# Qwiic_BME688.net
KiCad netlist of a schematic drawn in EAGLE
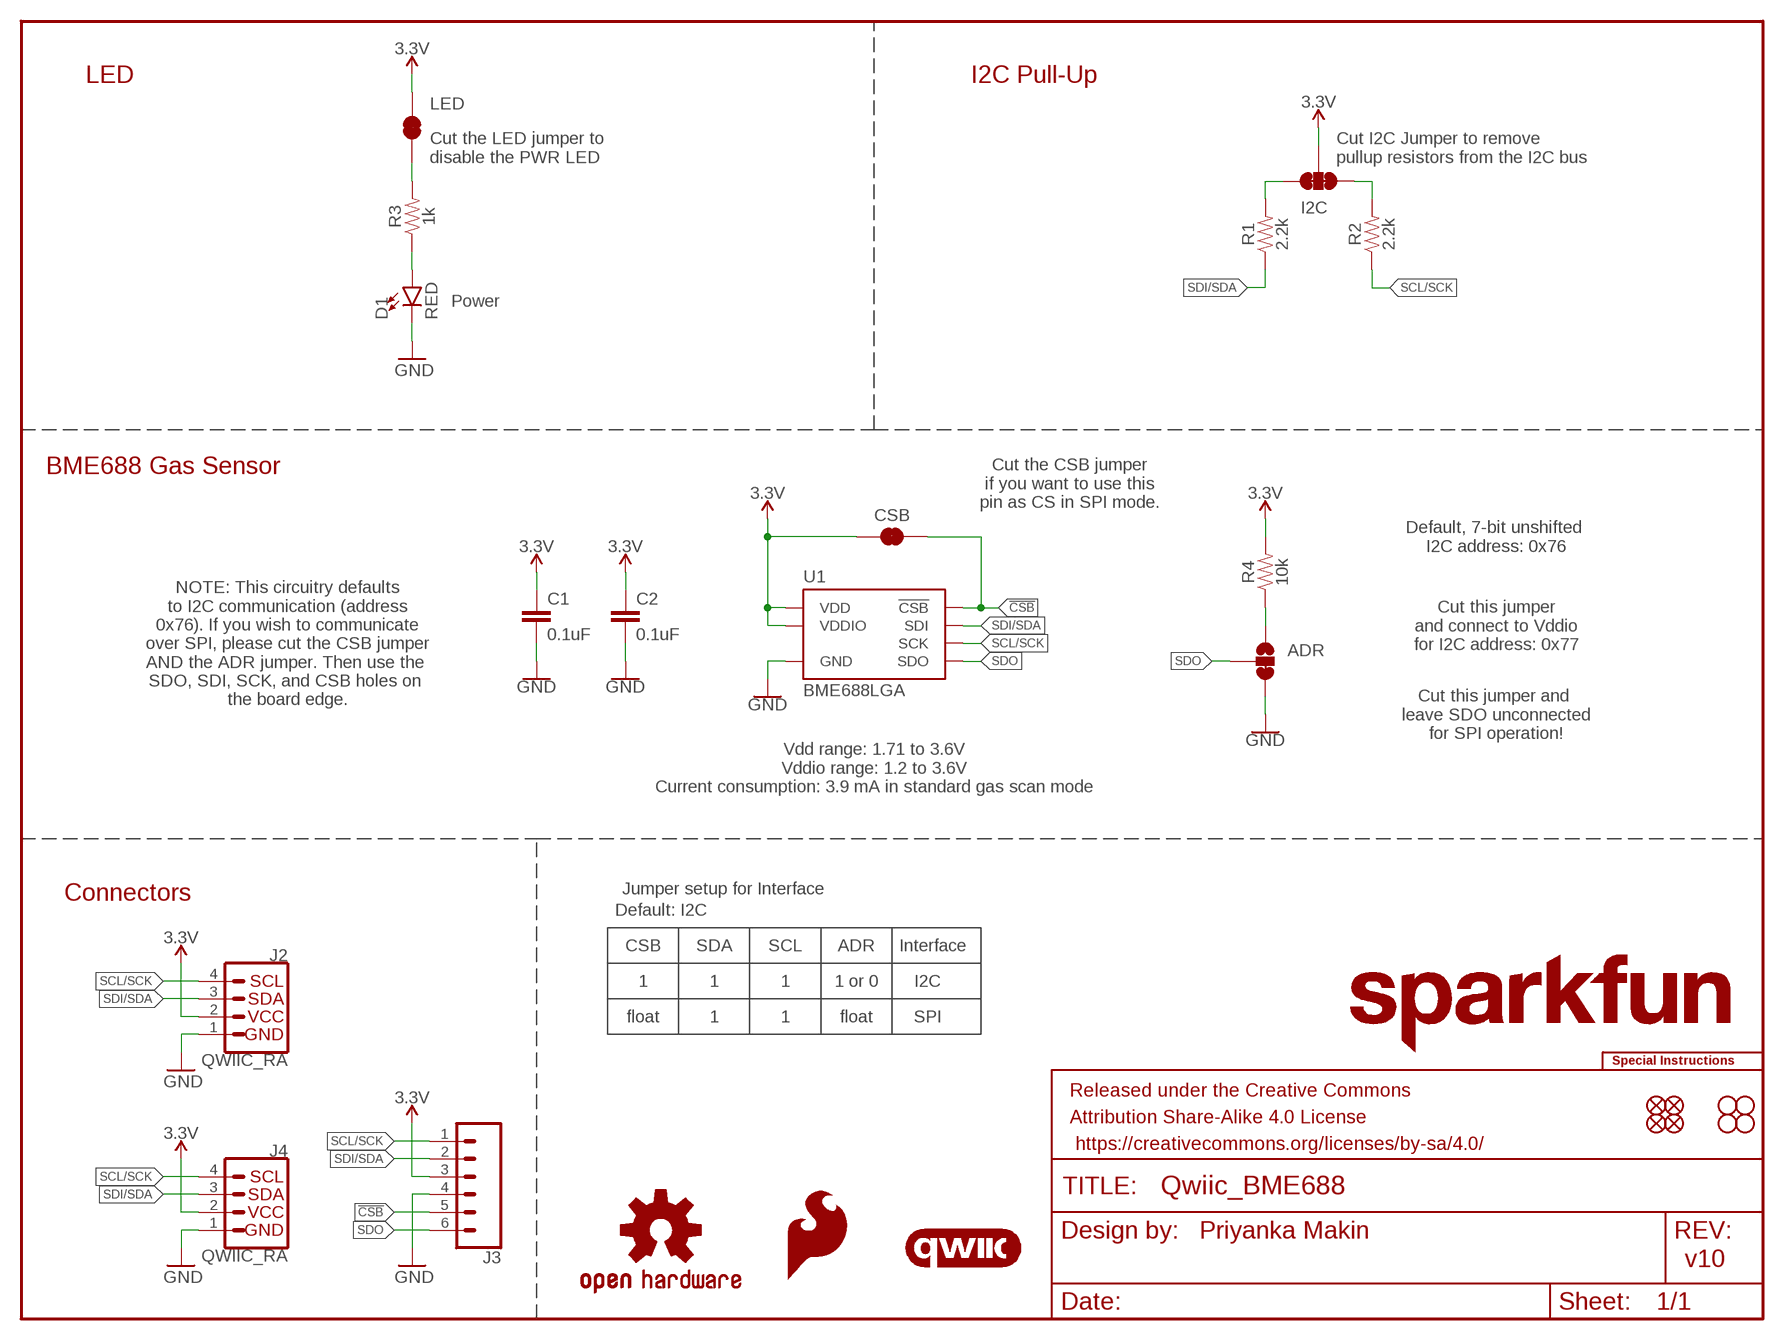
[diagram p0: schematic, sheet 1]

(export (version "E")
  (design (tool "Eeschema 10.0.6"))
  (components
    (comp (ref "ADR")
      (value "JUMPER-SMT_3_1-NC_TRACE_SILK")
      (footprint "eagle-import:SMT-JUMPER_3_1-NC_TRACE_SILK")
      (libsource (lib "eagle-import") (part "JUMPER-SMT_3_1-NC_TRACE_SILK"))
    )
    (comp (ref "C1")
      (value "0.1uF")
      (footprint "eagle-import:0603")
      (libsource (lib "eagle-import") (part "0.1UF-0603-100V-10%"))
    )
    (comp (ref "C2")
      (value "0.1uF")
      (footprint "eagle-import:0603")
      (libsource (lib "eagle-import") (part "0.1UF-0603-100V-10%"))
    )
    (comp (ref "CSB")
      (value "JUMPER-SMT_2_NC_TRACE_SILK")
      (footprint "eagle-import:SMT-JUMPER_2_NC_TRACE_SILK")
      (libsource (lib "eagle-import") (part "JUMPER-SMT_2_NC_TRACE_SILK"))
    )
    (comp (ref "D1")
      (value "RED")
      (footprint "eagle-import:LED-0603")
      (libsource (lib "eagle-import") (part "LED-RED0603"))
    )
    (comp (ref "FRAME1")
      (value "FRAME-LETTER")
      (footprint "eagle-import:CREATIVE_COMMONS")
      (libsource (lib "eagle-import") (part "FRAME-LETTER"))
    )
    (comp (ref "I2C")
      (value "JUMPER-SMT_3_2-NC_TRACE_SILK")
      (footprint "eagle-import:SMT-JUMPER_3_2-NC_TRACE_SILK")
      (libsource (lib "eagle-import") (part "JUMPER-SMT_3_2-NC_TRACE_SILK"))
    )
    (comp (ref "J2")
      (value "QWIIC_RA")
      (footprint "eagle-import:JST04_1MM_RA")
      (libsource (lib "eagle-import") (part "QWIIC_CONNECTORJS-1MM"))
    )
    (comp (ref "J3")
      (value "CONN_06NO_SILK_NO_POP")
      (footprint "eagle-import:1X06_NO_SILK")
      (libsource (lib "eagle-import") (part "CONN_06NO_SILK_NO_POP"))
    )
    (comp (ref "J4")
      (value "QWIIC_RA")
      (footprint "eagle-import:JST04_1MM_RA")
      (libsource (lib "eagle-import") (part "QWIIC_CONNECTORJS-1MM"))
    )
    (comp (ref "JP1")
      (value "FIDUCIALUFIDUCIAL")
      (footprint "eagle-import:FIDUCIAL-MICRO")
      (libsource (lib "eagle-import") (part "FIDUCIALUFIDUCIAL"))
    )
    (comp (ref "JP2")
      (value "FIDUCIALUFIDUCIAL")
      (footprint "eagle-import:FIDUCIAL-MICRO")
      (libsource (lib "eagle-import") (part "FIDUCIALUFIDUCIAL"))
    )
    (comp (ref "JP3")
      (value "STAND-OFF")
      (footprint "eagle-import:STAND-OFF")
      (libsource (lib "eagle-import") (part "STAND-OFF"))
    )
    (comp (ref "JP4")
      (value "STAND-OFF")
      (footprint "eagle-import:STAND-OFF")
      (libsource (lib "eagle-import") (part "STAND-OFF"))
    )
    (comp (ref "JP5")
      (value "FIDUCIALUFIDUCIAL")
      (footprint "eagle-import:FIDUCIAL-MICRO")
      (libsource (lib "eagle-import") (part "FIDUCIALUFIDUCIAL"))
    )
    (comp (ref "JP6")
      (value "FIDUCIALUFIDUCIAL")
      (footprint "eagle-import:FIDUCIAL-MICRO")
      (libsource (lib "eagle-import") (part "FIDUCIALUFIDUCIAL"))
    )
    (comp (ref "JP7")
      (value "STAND-OFF")
      (footprint "eagle-import:STAND-OFF")
      (libsource (lib "eagle-import") (part "STAND-OFF"))
    )
    (comp (ref "JP8")
      (value "STAND-OFF")
      (footprint "eagle-import:STAND-OFF")
      (libsource (lib "eagle-import") (part "STAND-OFF"))
    )
    (comp (ref "LED")
      (value "JUMPER-SMT_2_NC_TRACE_SILK")
      (footprint "eagle-import:SMT-JUMPER_2_NC_TRACE_SILK")
      (libsource (lib "eagle-import") (part "JUMPER-SMT_2_NC_TRACE_SILK"))
    )
    (comp (ref "LOGO1")
      (value "SPECIAL_INSTRUCTIONS-ORDERING")
      (footprint "eagle-import:ORDERING_INSTRUCTIONS")
      (libsource (lib "eagle-import") (part "SPECIAL_INSTRUCTIONS-ORDERING"))
    )
    (comp (ref "LOGO2")
      (value "QWIIC_LOGO_5MM")
      (footprint "eagle-import:QWIIC_5MM")
      (libsource (lib "eagle-import") (part "QWIIC_LOGO_5MM"))
    )
    (comp (ref "LOGO3")
      (value "SFE_LOGO_NAME.1_INCH")
      (footprint "eagle-import:SFE_LOGO_NAME_.1")
      (libsource (lib "eagle-import") (part "SFE_LOGO_NAME.1_INCH"))
    )
    (comp (ref "LOGO4")
      (value "SFE_LOGO_FLAME.1_INCH")
      (footprint "eagle-import:SFE_LOGO_FLAME_.1")
      (libsource (lib "eagle-import") (part "SFE_LOGO_FLAME.1_INCH"))
    )
    (comp (ref "LOGO5")
      (value "OSHW-LOGOS")
      (footprint "eagle-import:OSHW-LOGO-S")
      (libsource (lib "eagle-import") (part "OSHW-LOGOS"))
    )
    (comp (ref "LOGO6")
      (value "SFE_LOGO_NAME.1_INCH")
      (footprint "eagle-import:SFE_LOGO_NAME_.1")
      (libsource (lib "eagle-import") (part "SFE_LOGO_NAME.1_INCH"))
    )
    (comp (ref "R1")
      (value "2.2k")
      (footprint "eagle-import:0603")
      (libsource (lib "eagle-import") (part "2.2KOHM-0603-1/10W-1%"))
    )
    (comp (ref "R2")
      (value "2.2k")
      (footprint "eagle-import:0603")
      (libsource (lib "eagle-import") (part "2.2KOHM-0603-1/10W-1%"))
    )
    (comp (ref "R3")
      (value "1k")
      (footprint "eagle-import:0603")
      (libsource (lib "eagle-import") (part "1KOHM-0603-1/10W-1%"))
    )
    (comp (ref "R4")
      (value "10k")
      (footprint "eagle-import:0603")
      (libsource (lib "eagle-import") (part "10KOHM-0603-1/10W-1%"))
    )
    (comp (ref "U1")
      (value "BME688LGA")
      (footprint "eagle-import:LGA_8PIN")
      (libsource (lib "eagle-import") (part "BME688LGA"))
    )
  )
  (nets
    (net (code "1") (name "/~{CSB}") (class "Default")
      (node (ref "CSB") (pin "2") (pinfunction "2_2") (pintype "passive"))
      (node (ref "J3") (pin "5") (pinfunction "5_5") (pintype "passive"))
      (node (ref "U1") (pin "2") (pinfunction "~{CSB}_2") (pintype "power_in"))
    )
    (net (code "2") (name "3.3V") (class "Default")
      (node (ref "C1") (pin "1") (pinfunction "1_1") (pintype "passive"))
      (node (ref "C2") (pin "1") (pinfunction "1_1") (pintype "passive"))
      (node (ref "CSB") (pin "1") (pinfunction "1_1") (pintype "passive"))
      (node (ref "I2C") (pin "2") (pinfunction "2_2") (pintype "passive"))
      (node (ref "J2") (pin "2") (pinfunction "2_2") (pintype "power_in"))
      (node (ref "J3") (pin "3") (pinfunction "3_3") (pintype "passive"))
      (node (ref "J4") (pin "2") (pinfunction "2_2") (pintype "power_in"))
      (node (ref "LED") (pin "2") (pinfunction "2_2") (pintype "passive"))
      (node (ref "R4") (pin "2") (pinfunction "2_2") (pintype "passive"))
      (node (ref "U1") (pin "6") (pinfunction "VDDIO_6") (pintype "power_in"))
      (node (ref "U1") (pin "8") (pinfunction "VDD_8") (pintype "power_in"))
    )
    (net (code "3") (name "GND") (class "Default")
      (node (ref "ADR") (pin "3") (pinfunction "3_3") (pintype "passive"))
      (node (ref "C1") (pin "2") (pinfunction "2_2") (pintype "passive"))
      (node (ref "C2") (pin "2") (pinfunction "2_2") (pintype "passive"))
      (node (ref "D1") (pin "C") (pinfunction "C_C") (pintype "passive"))
      (node (ref "J2") (pin "1") (pinfunction "1_1") (pintype "power_in"))
      (node (ref "J3") (pin "4") (pinfunction "4_4") (pintype "passive"))
      (node (ref "J4") (pin "1") (pinfunction "1_1") (pintype "power_in"))
      (node (ref "U1") (pin "1") (pinfunction "GND_1") (pintype "power_in"))
      (node (ref "U1") (pin "7") (pinfunction "GND_7") (pintype "power_in"))
    )
    (net (code "4") (name "Net-(ADR-Pad1)") (class "Default")
      (node (ref "ADR") (pin "1") (pinfunction "1_1") (pintype "passive"))
      (node (ref "R4") (pin "1") (pinfunction "1_1") (pintype "passive"))
    )
    (net (code "5") (name "Net-(D1-PadA)") (class "Default")
      (node (ref "D1") (pin "A") (pinfunction "A_A") (pintype "passive"))
      (node (ref "R3") (pin "1") (pinfunction "1_1") (pintype "passive"))
    )
    (net (code "6") (name "Net-(I2C-Pad1)") (class "Default")
      (node (ref "I2C") (pin "1") (pinfunction "1_1") (pintype "passive"))
      (node (ref "R2") (pin "2") (pinfunction "2_2") (pintype "passive"))
    )
    (net (code "7") (name "Net-(I2C-Pad3)") (class "Default")
      (node (ref "I2C") (pin "3") (pinfunction "3_3") (pintype "passive"))
      (node (ref "R1") (pin "2") (pinfunction "2_2") (pintype "passive"))
    )
    (net (code "8") (name "Net-(LED-Pad1)") (class "Default")
      (node (ref "LED") (pin "1") (pinfunction "1_1") (pintype "passive"))
      (node (ref "R3") (pin "2") (pinfunction "2_2") (pintype "passive"))
    )
    (net (code "9") (name "SCL{slash}SCK") (class "Default")
      (node (ref "J2") (pin "4") (pinfunction "4_4") (pintype "passive"))
      (node (ref "J3") (pin "1") (pinfunction "1_1") (pintype "passive"))
      (node (ref "J4") (pin "4") (pinfunction "4_4") (pintype "passive"))
      (node (ref "R2") (pin "1") (pinfunction "1_1") (pintype "passive"))
      (node (ref "U1") (pin "4") (pinfunction "SCK_4") (pintype "bidirectional"))
    )
    (net (code "10") (name "SDI{slash}SDA") (class "Default")
      (node (ref "J2") (pin "3") (pinfunction "3_3") (pintype "passive"))
      (node (ref "J3") (pin "2") (pinfunction "2_2") (pintype "passive"))
      (node (ref "J4") (pin "3") (pinfunction "3_3") (pintype "passive"))
      (node (ref "R1") (pin "1") (pinfunction "1_1") (pintype "passive"))
      (node (ref "U1") (pin "3") (pinfunction "SDI_3") (pintype "bidirectional"))
    )
    (net (code "11") (name "SDO") (class "Default")
      (node (ref "ADR") (pin "2") (pinfunction "2_2") (pintype "passive"))
      (node (ref "J3") (pin "6") (pinfunction "6_6") (pintype "passive"))
      (node (ref "U1") (pin "5") (pinfunction "SDO_5") (pintype "power_in"))
    )
  )
)
